# rapidshark-main-display-butt-breakout-mk.net
KiCad netlist of a schematic drawn in EAGLE
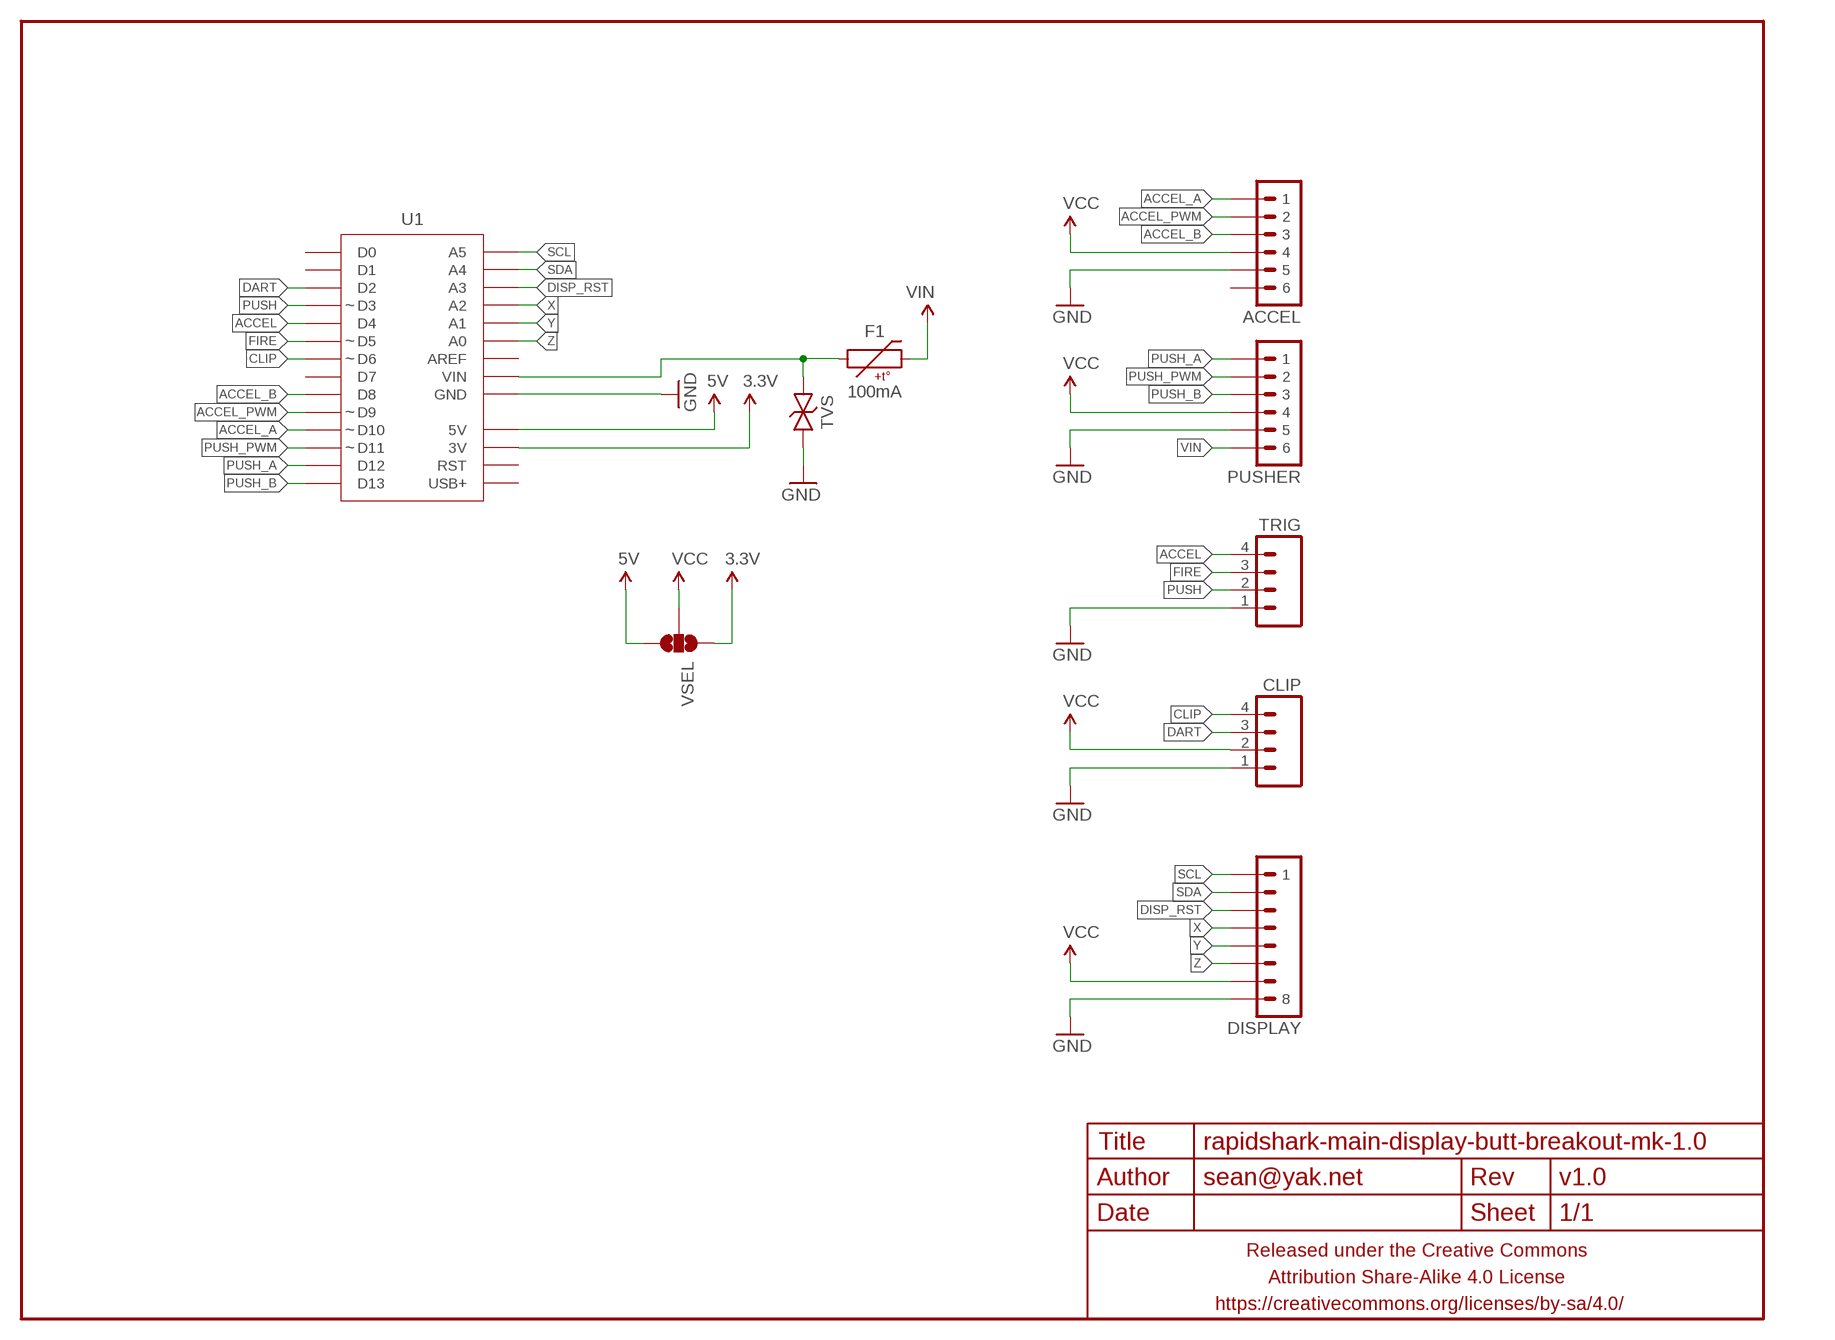
[diagram p0: schematic, sheet 1]

(export (version "E")
  (design (tool "Eeschema 10.0.6"))
  (components
    (comp (ref "ACCEL")
      (value "M06JST-PH-PTH-VERT")
      (footprint "eagle-import:JST-6-PH-VERT-PTH")
      (libsource (lib "eagle-import") (part "M06JST-PH-PTH-VERT"))
    )
    (comp (ref "CLIP")
      (value "M04JST-PTH-VERT")
      (footprint "eagle-import:JST-4-PH-VERT-PTH")
      (libsource (lib "eagle-import") (part "M04JST-PTH-VERT"))
    )
    (comp (ref "DISPLAY")
      (value "M08JST-PH-VERT-PTH")
      (footprint "eagle-import:JST-8-VERT-PTH")
      (libsource (lib "eagle-import") (part "M08JST-PH-VERT-PTH"))
    )
    (comp (ref "F1")
      (value "100mA")
      (footprint "eagle-import:PTC-1206")
      (libsource (lib "eagle-import") (part "PTCSMD"))
    )
    (comp (ref "FRAME1")
      (value "FRAME-LETTERNO_PACKAGE")
      (footprint "eagle-import:DUMMY")
      (fields (field (name "DESIGNER") "sean@yak.net") (field (name "VERSION") "v1.0"))
      (libsource (lib "eagle-import") (part "FRAME-LETTERNO_PACKAGE"))
    )
    (comp (ref "PUSHER")
      (value "M06JST-PH-PTH-VERT")
      (footprint "eagle-import:JST-6-PH-VERT-PTH")
      (libsource (lib "eagle-import") (part "M06JST-PH-PTH-VERT"))
    )
    (comp (ref "TRIG")
      (value "M04JST-PTH-VERT")
      (footprint "eagle-import:JST-4-PH-VERT-PTH")
      (libsource (lib "eagle-import") (part "M04JST-PTH-VERT"))
    )
    (comp (ref "TVS")
      (value "TVSSMA")
      (footprint "eagle-import:SMA-DIODE-TVS-BIDIR")
      (libsource (lib "eagle-import") (part "TVSSMA"))
    )
    (comp (ref "U1")
      (value "ADAFRUIT_METRO_MININOSILK-AMBI2")
      (footprint "eagle-import:ADAFRUIT_METRO_MINI_BACK")
      (libsource (lib "eagle-import") (part "ADAFRUIT_METRO_MININOSILK-AMBI2"))
    )
    (comp (ref "VSEL")
      (value "JUMPER-PAD-3-NOFULL_BOX_SILK")
      (footprint "eagle-import:PAD-JUMPER-3-NO_YES_SILK_FULL_BOX")
      (libsource (lib "eagle-import") (part "JUMPER-PAD-3-NOFULL_BOX_SILK"))
    )
  )
  (nets
    (net (code "1") (name "3.3V") (class "Default")
      (node (ref "U1") (pin "17") (pinfunction "3V_17") (pintype "bidirectional"))
      (node (ref "VSEL") (pin "1") (pinfunction "1_1") (pintype "passive"))
    )
    (net (code "2") (name "5V") (class "Default")
      (node (ref "U1") (pin "18") (pinfunction "5V_18") (pintype "bidirectional"))
      (node (ref "VSEL") (pin "3") (pinfunction "3_3") (pintype "passive"))
    )
    (net (code "3") (name "ACCEL") (class "Default")
      (node (ref "TRIG") (pin "4") (pinfunction "4_4") (pintype "passive"))
      (node (ref "U1") (pin "5") (pinfunction "D4_5") (pintype "bidirectional"))
    )
    (net (code "4") (name "ACCEL_A") (class "Default")
      (node (ref "ACCEL") (pin "1") (pinfunction "1_1") (pintype "passive"))
      (node (ref "U1") (pin "11") (pinfunction "D10_11") (pintype "bidirectional"))
    )
    (net (code "5") (name "ACCEL_B") (class "Default")
      (node (ref "ACCEL") (pin "3") (pinfunction "3_3") (pintype "passive"))
      (node (ref "U1") (pin "9") (pinfunction "D8_9") (pintype "bidirectional"))
    )
    (net (code "6") (name "ACCEL_PWM") (class "Default")
      (node (ref "ACCEL") (pin "2") (pinfunction "2_2") (pintype "passive"))
      (node (ref "U1") (pin "10") (pinfunction "D9_10") (pintype "bidirectional"))
    )
    (net (code "7") (name "CLIP") (class "Default")
      (node (ref "CLIP") (pin "4") (pinfunction "4_4") (pintype "passive"))
      (node (ref "U1") (pin "7") (pinfunction "D6_7") (pintype "bidirectional"))
    )
    (net (code "8") (name "DART") (class "Default")
      (node (ref "CLIP") (pin "3") (pinfunction "3_3") (pintype "passive"))
      (node (ref "U1") (pin "3") (pinfunction "D2_3") (pintype "bidirectional"))
    )
    (net (code "9") (name "DISP_RST") (class "Default")
      (node (ref "DISPLAY") (pin "3") (pinfunction "3_3") (pintype "passive"))
      (node (ref "U1") (pin "26") (pinfunction "A3_26") (pintype "bidirectional"))
    )
    (net (code "10") (name "FIRE") (class "Default")
      (node (ref "TRIG") (pin "3") (pinfunction "3_3") (pintype "passive"))
      (node (ref "U1") (pin "6") (pinfunction "D5_6") (pintype "bidirectional"))
    )
    (net (code "11") (name "GND") (class "Default")
      (node (ref "ACCEL") (pin "5") (pinfunction "5_5") (pintype "passive"))
      (node (ref "CLIP") (pin "1") (pinfunction "1_1") (pintype "passive"))
      (node (ref "DISPLAY") (pin "8") (pinfunction "8_8") (pintype "passive"))
      (node (ref "PUSHER") (pin "5") (pinfunction "5_5") (pintype "passive"))
      (node (ref "TRIG") (pin "1") (pinfunction "1_1") (pintype "passive"))
      (node (ref "TVS") (pin "1") (pinfunction "1_1") (pintype "passive"))
      (node (ref "U1") (pin "19") (pinfunction "GND_19") (pintype "bidirectional"))
      (node (ref "U1") (pin "20") (pinfunction "GND_20") (pintype "bidirectional"))
    )
    (net (code "12") (name "Net-(U1-VIN)") (class "Default")
      (node (ref "F1") (pin "1") (pinfunction "1_1") (pintype "passive"))
      (node (ref "TVS") (pin "2") (pinfunction "2_2") (pintype "passive"))
      (node (ref "U1") (pin "21") (pinfunction "VIN_21") (pintype "bidirectional"))
    )
    (net (code "13") (name "PUSH") (class "Default")
      (node (ref "TRIG") (pin "2") (pinfunction "2_2") (pintype "passive"))
      (node (ref "U1") (pin "4") (pinfunction "D3_4") (pintype "bidirectional"))
    )
    (net (code "14") (name "PUSH_A") (class "Default")
      (node (ref "PUSHER") (pin "1") (pinfunction "1_1") (pintype "passive"))
      (node (ref "U1") (pin "13") (pinfunction "D12_13") (pintype "bidirectional"))
    )
    (net (code "15") (name "PUSH_B") (class "Default")
      (node (ref "PUSHER") (pin "3") (pinfunction "3_3") (pintype "passive"))
      (node (ref "U1") (pin "14") (pinfunction "D13_14") (pintype "bidirectional"))
    )
    (net (code "16") (name "PUSH_PWM") (class "Default")
      (node (ref "PUSHER") (pin "2") (pinfunction "2_2") (pintype "passive"))
      (node (ref "U1") (pin "12") (pinfunction "D11_12") (pintype "bidirectional"))
    )
    (net (code "17") (name "SCL") (class "Default")
      (node (ref "DISPLAY") (pin "1") (pinfunction "1_1") (pintype "passive"))
      (node (ref "U1") (pin "28") (pinfunction "A5_28") (pintype "bidirectional"))
    )
    (net (code "18") (name "SDA") (class "Default")
      (node (ref "DISPLAY") (pin "2") (pinfunction "2_2") (pintype "passive"))
      (node (ref "U1") (pin "27") (pinfunction "A4_27") (pintype "bidirectional"))
    )
    (net (code "19") (name "VCC") (class "Default")
      (node (ref "ACCEL") (pin "4") (pinfunction "4_4") (pintype "passive"))
      (node (ref "CLIP") (pin "2") (pinfunction "2_2") (pintype "passive"))
      (node (ref "DISPLAY") (pin "7") (pinfunction "7_7") (pintype "passive"))
      (node (ref "PUSHER") (pin "4") (pinfunction "4_4") (pintype "passive"))
      (node (ref "VSEL") (pin "2") (pinfunction "2_2") (pintype "passive"))
    )
    (net (code "20") (name "VIN") (class "Default")
      (node (ref "F1") (pin "2") (pinfunction "2_2") (pintype "passive"))
      (node (ref "PUSHER") (pin "6") (pinfunction "6_6") (pintype "passive"))
    )
    (net (code "21") (name "X") (class "Default")
      (node (ref "DISPLAY") (pin "4") (pinfunction "4_4") (pintype "passive"))
      (node (ref "U1") (pin "25") (pinfunction "A2_25") (pintype "bidirectional"))
    )
    (net (code "22") (name "Y") (class "Default")
      (node (ref "DISPLAY") (pin "5") (pinfunction "5_5") (pintype "passive"))
      (node (ref "U1") (pin "24") (pinfunction "A1_24") (pintype "bidirectional"))
    )
    (net (code "23") (name "Z") (class "Default")
      (node (ref "DISPLAY") (pin "6") (pinfunction "6_6") (pintype "passive"))
      (node (ref "U1") (pin "23") (pinfunction "A0_23") (pintype "bidirectional"))
    )
    (net (code "24") (name "unconnected-(ACCEL-Pad6)") (class "Default")
      (node (ref "ACCEL") (pin "6") (pinfunction "6_6") (pintype "passive"))
    )
    (net (code "25") (name "unconnected-(U1-AREF-Pad22)") (class "Default")
      (node (ref "U1") (pin "22") (pinfunction "AREF_22") (pintype "bidirectional"))
    )
    (net (code "26") (name "unconnected-(U1-D0-Pad1)") (class "Default")
      (node (ref "U1") (pin "1") (pinfunction "D0_1") (pintype "bidirectional"))
    )
    (net (code "27") (name "unconnected-(U1-D1-Pad2)") (class "Default")
      (node (ref "U1") (pin "2") (pinfunction "D1_2") (pintype "bidirectional"))
    )
    (net (code "28") (name "unconnected-(U1-D7-Pad8)") (class "Default")
      (node (ref "U1") (pin "8") (pinfunction "D7_8") (pintype "bidirectional"))
    )
    (net (code "29") (name "unconnected-(U1-RST-Pad16)") (class "Default")
      (node (ref "U1") (pin "16") (pinfunction "RST_16") (pintype "bidirectional"))
    )
    (net (code "30") (name "unconnected-(U1-USB+-Pad15)") (class "Default")
      (node (ref "U1") (pin "15") (pinfunction "USB+_15") (pintype "bidirectional"))
    )
  )
)
